# PCB_Capacitor_V1.net
KiCad netlist of a schematic drawn in EAGLE
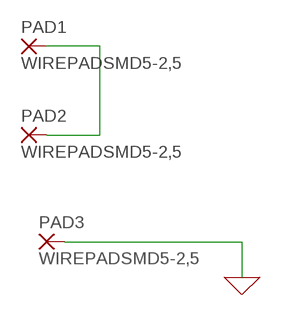
[diagram p0: schematic, sheet 1]

(export (version "E")
  (design (tool "Eeschema 10.0.6"))
  (components
    (comp (ref "PAD1")
      (value "WIREPADSMD5-2,5")
      (footprint "eagle-import:5-2,5")
      (libsource (lib "eagle-import") (part "WIREPADSMD5-2,5"))
    )
    (comp (ref "PAD2")
      (value "WIREPADSMD5-2,5")
      (footprint "eagle-import:5-2,5")
      (libsource (lib "eagle-import") (part "WIREPADSMD5-2,5"))
    )
    (comp (ref "PAD3")
      (value "WIREPADSMD5-2,5")
      (footprint "eagle-import:5-2,5")
      (libsource (lib "eagle-import") (part "WIREPADSMD5-2,5"))
    )
  )
  (nets
    (net (code "1") (name "GND") (class "Default")
      (node (ref "PAD3") (pin "1") (pinfunction "P_1") (pintype "passive"))
    )
    (net (code "2") (name "Net-(PAD1-P)") (class "Default")
      (node (ref "PAD1") (pin "1") (pinfunction "P_1") (pintype "passive"))
      (node (ref "PAD2") (pin "1") (pinfunction "P_1") (pintype "passive"))
    )
  )
)
